# satstep6600.net
KiCad netlist of a schematic drawn in EAGLE
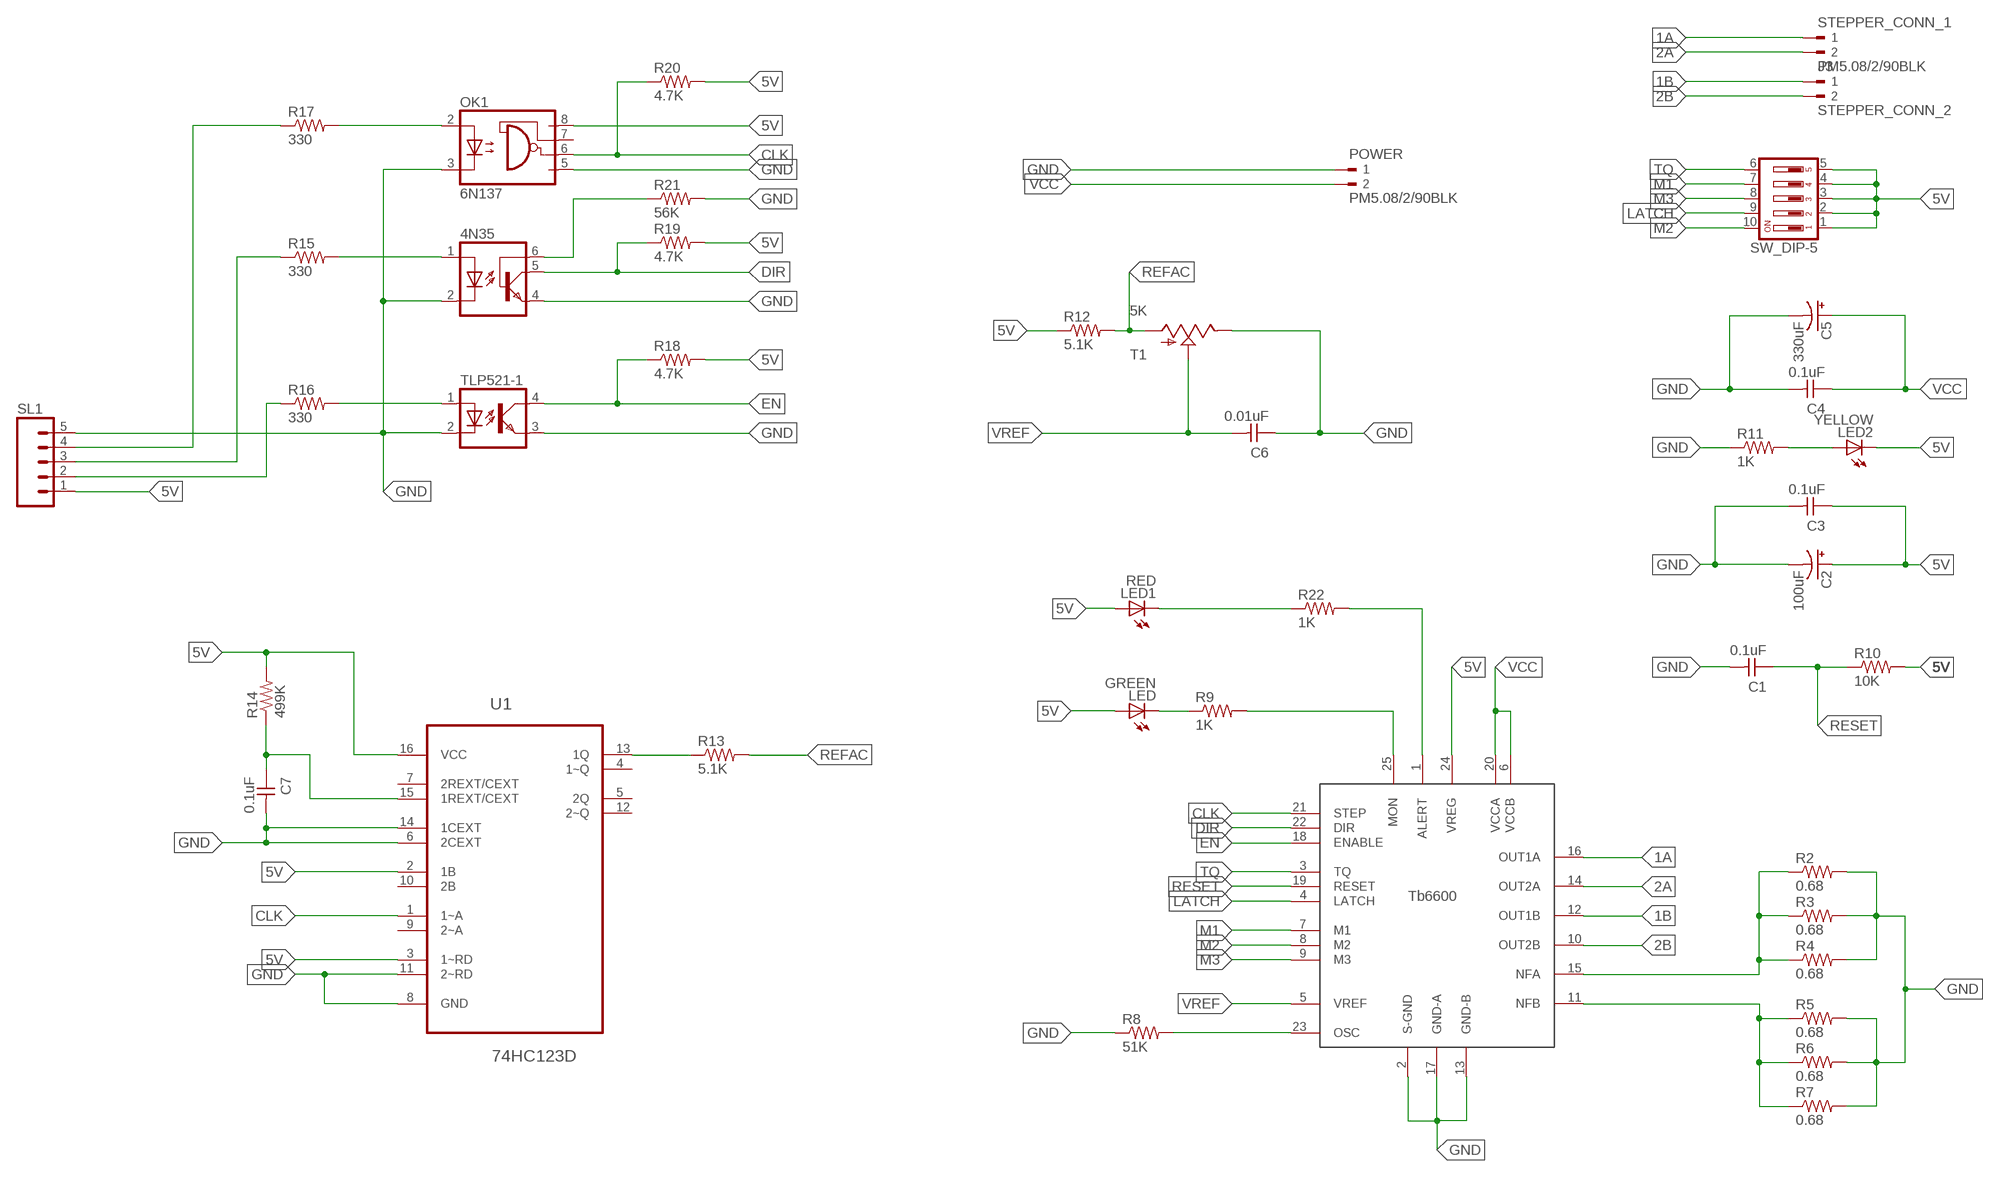
[diagram p0: schematic, sheet 1]

(export (version "E")
  (design (tool "Eeschema 10.0.6"))
  (components
    (comp (ref "4N35")
      (value "4N35")
      (footprint "eagle-import:DIL06")
      (libsource (lib "eagle-import") (part "4N35"))
    )
    (comp (ref "C1")
      (value "0.1uF")
      (footprint "eagle-import:1206")
      (libsource (lib "eagle-import") (part "UNPOLARIZED_CAPACITOR1206"))
    )
    (comp (ref "C2")
      (value "100uF")
      (footprint "eagle-import:PANASONIC_C")
      (libsource (lib "eagle-import") (part "CAP_POLC"))
    )
    (comp (ref "C3")
      (value "0.1uF")
      (footprint "eagle-import:1206")
      (libsource (lib "eagle-import") (part "UNPOLARIZED_CAPACITOR1206"))
    )
    (comp (ref "C4")
      (value "0.1uF")
      (footprint "eagle-import:1206")
      (libsource (lib "eagle-import") (part "UNPOLARIZED_CAPACITOR1206"))
    )
    (comp (ref "C5")
      (value "330uF")
      (footprint "eagle-import:CPOL-RADIAL-1000UF-63V")
      (libsource (lib "eagle-import") (part "CAP_POLPTH3"))
    )
    (comp (ref "C6")
      (value "0.01uF")
      (footprint "eagle-import:1206")
      (libsource (lib "eagle-import") (part "UNPOLARIZED_CAPACITOR1206"))
    )
    (comp (ref "C7")
      (value "0.1uF")
      (footprint "eagle-import:1206")
      (libsource (lib "eagle-import") (part "UNPOLARIZED_CAPACITOR1206"))
    )
    (comp (ref "J3")
      (value "STEPPER_CONN_2")
      (footprint "eagle-import:WEIDMULLER_PM5.08_2")
      (fields (field (name "MPN") "PM5.08/2/90 BLK"))
      (libsource (lib "eagle-import") (part "PM5.08/2/90BLK"))
    )
    (comp (ref "LED")
      (value "GREEN")
      (footprint "eagle-import:1206")
      (libsource (lib "eagle-import") (part "LED1206"))
    )
    (comp (ref "LED1")
      (value "RED")
      (footprint "eagle-import:1206")
      (libsource (lib "eagle-import") (part "LED1206"))
    )
    (comp (ref "LED2")
      (value "YELLOW")
      (footprint "eagle-import:1206")
      (libsource (lib "eagle-import") (part "LED1206"))
    )
    (comp (ref "OK1")
      (value "6N137")
      (footprint "eagle-import:DIL08")
      (libsource (lib "eagle-import") (part "6N137"))
    )
    (comp (ref "POWER")
      (value "PM5.08/2/90BLK")
      (footprint "eagle-import:WEIDMULLER_PM5.08_2")
      (fields (field (name "MPN") "PM5.08/2/90 BLK"))
      (libsource (lib "eagle-import") (part "PM5.08/2/90BLK"))
    )
    (comp (ref "R2")
      (value "0.68")
      (footprint "eagle-import:2512")
      (libsource (lib "eagle-import") (part "0.001OHM-3W-1%(2512)3W/1%"))
    )
    (comp (ref "R3")
      (value "0.68")
      (footprint "eagle-import:2512")
      (libsource (lib "eagle-import") (part "0.001OHM-3W-1%(2512)3W/1%"))
    )
    (comp (ref "R4")
      (value "0.68")
      (footprint "eagle-import:2512")
      (libsource (lib "eagle-import") (part "0.001OHM-3W-1%(2512)3W/1%"))
    )
    (comp (ref "R5")
      (value "0.68")
      (footprint "eagle-import:2512")
      (libsource (lib "eagle-import") (part "0.001OHM-3W-1%(2512)3W/1%"))
    )
    (comp (ref "R6")
      (value "0.68")
      (footprint "eagle-import:2512")
      (libsource (lib "eagle-import") (part "0.001OHM-3W-1%(2512)3W/1%"))
    )
    (comp (ref "R7")
      (value "0.68")
      (footprint "eagle-import:2512")
      (libsource (lib "eagle-import") (part "0.001OHM-3W-1%(2512)3W/1%"))
    )
    (comp (ref "R8")
      (value "51K")
      (footprint "eagle-import:R1206")
      (libsource (lib "eagle-import") (part "RES-US1206"))
    )
    (comp (ref "R9")
      (value "1K")
      (footprint "eagle-import:R1206")
      (libsource (lib "eagle-import") (part "RES-US1206"))
    )
    (comp (ref "R10")
      (value "10K")
      (footprint "eagle-import:R1206")
      (libsource (lib "eagle-import") (part "RES-US1206"))
    )
    (comp (ref "R11")
      (value "1K")
      (footprint "eagle-import:R1206")
      (libsource (lib "eagle-import") (part "RES-US1206"))
    )
    (comp (ref "R12")
      (value "5.1K")
      (footprint "eagle-import:R1206")
      (libsource (lib "eagle-import") (part "RES-US1206"))
    )
    (comp (ref "R13")
      (value "5.1K")
      (footprint "eagle-import:R1206")
      (libsource (lib "eagle-import") (part "RES-US1206"))
    )
    (comp (ref "R14")
      (value "499K")
      (footprint "eagle-import:R1206")
      (libsource (lib "eagle-import") (part "RES-US1206"))
    )
    (comp (ref "R15")
      (value "330")
      (footprint "eagle-import:R1206")
      (libsource (lib "eagle-import") (part "RES-US1206"))
    )
    (comp (ref "R16")
      (value "330")
      (footprint "eagle-import:R1206")
      (libsource (lib "eagle-import") (part "RES-US1206"))
    )
    (comp (ref "R17")
      (value "330")
      (footprint "eagle-import:R1206")
      (libsource (lib "eagle-import") (part "RES-US1206"))
    )
    (comp (ref "R18")
      (value "4.7K")
      (footprint "eagle-import:R1206")
      (libsource (lib "eagle-import") (part "RES-US1206"))
    )
    (comp (ref "R19")
      (value "4.7K")
      (footprint "eagle-import:R1206")
      (libsource (lib "eagle-import") (part "RES-US1206"))
    )
    (comp (ref "R20")
      (value "4.7K")
      (footprint "eagle-import:R1206")
      (libsource (lib "eagle-import") (part "RES-US1206"))
    )
    (comp (ref "R21")
      (value "56K")
      (footprint "eagle-import:R1206")
      (libsource (lib "eagle-import") (part "RES-US1206"))
    )
    (comp (ref "R22")
      (value "1K")
      (footprint "eagle-import:R1206")
      (libsource (lib "eagle-import") (part "RES-US1206"))
    )
    (comp (ref "SL1")
      (value "M05")
      (footprint "eagle-import:05P")
      (libsource (lib "eagle-import") (part "M05"))
    )
    (comp (ref "STEPPER_CONN_1")
      (value "PM5.08/2/90BLK")
      (footprint "eagle-import:WEIDMULLER_PM5.08_2")
      (fields (field (name "MPN") "PM5.08/2/90 BLK"))
      (libsource (lib "eagle-import") (part "PM5.08/2/90BLK"))
    )
    (comp (ref "SW_DIP-5")
      (value "SD4-05")
      (footprint "eagle-import:SD4-05")
      (libsource (lib "eagle-import") (part "SD4-05"))
    )
    (comp (ref "T1")
      (value "5K")
      (footprint "eagle-import:TS53YL104MR10_TRIMMER")
      (libsource (lib "eagle-import") (part "TS53YL104MR10-TRIMMER"))
    )
    (comp (ref "TLP521-1")
      (value "PC817")
      (footprint "eagle-import:DIL04")
      (libsource (lib "eagle-import") (part "PC817"))
    )
    (comp (ref "U$1")
      (value "TB6600HG")
      (footprint "eagle-import:P-HZIP25-1.00G")
      (libsource (lib "eagle-import") (part "TB6600HG"))
    )
    (comp (ref "U1")
      (value "74HC123D")
      (footprint "eagle-import:SOIC127P600X175-16N")
      (libsource (lib "eagle-import") (part "74HC123D"))
    )
  )
  (nets
    (net (code "1") (name "1A") (class "Default")
      (node (ref "STEPPER_CONN_1") (pin "1") (pinfunction "1_1") (pintype "passive"))
      (node (ref "U$1") (pin "16") (pinfunction "OUT1A_16") (pintype "output"))
    )
    (net (code "2") (name "1B") (class "Default")
      (node (ref "J3") (pin "1") (pinfunction "1_1") (pintype "passive"))
      (node (ref "U$1") (pin "12") (pinfunction "OUT1B_12") (pintype "output"))
    )
    (net (code "3") (name "2A") (class "Default")
      (node (ref "STEPPER_CONN_1") (pin "2") (pinfunction "2_2") (pintype "passive"))
      (node (ref "U$1") (pin "14") (pinfunction "OUT2A_14") (pintype "output"))
    )
    (net (code "4") (name "2B") (class "Default")
      (node (ref "J3") (pin "2") (pinfunction "2_2") (pintype "passive"))
      (node (ref "U$1") (pin "10") (pinfunction "OUT2B_10") (pintype "output"))
    )
    (net (code "5") (name "5V") (class "Default")
      (node (ref "C2") (pin "+") (pinfunction "+_+") (pintype "passive"))
      (node (ref "C3") (pin "1") (pinfunction "1_1") (pintype "passive"))
      (node (ref "LED") (pin "1") (pinfunction "A_1") (pintype "passive"))
      (node (ref "LED1") (pin "1") (pinfunction "A_1") (pintype "passive"))
      (node (ref "LED2") (pin "2") (pinfunction "C_2") (pintype "passive"))
      (node (ref "OK1") (pin "8") (pinfunction "VCC_8") (pintype "passive"))
      (node (ref "R10") (pin "2") (pinfunction "2_2") (pintype "passive"))
      (node (ref "R12") (pin "1") (pinfunction "1_1") (pintype "passive"))
      (node (ref "R14") (pin "2") (pinfunction "2_2") (pintype "passive"))
      (node (ref "R18") (pin "2") (pinfunction "2_2") (pintype "passive"))
      (node (ref "R19") (pin "2") (pinfunction "2_2") (pintype "passive"))
      (node (ref "R20") (pin "2") (pinfunction "2_2") (pintype "passive"))
      (node (ref "SL1") (pin "1") (pinfunction "1_1") (pintype "passive"))
      (node (ref "SW_DIP-5") (pin "1") (pinfunction "1_1") (pintype "passive"))
      (node (ref "SW_DIP-5") (pin "2") (pinfunction "2_2") (pintype "passive"))
      (node (ref "SW_DIP-5") (pin "3") (pinfunction "3_3") (pintype "passive"))
      (node (ref "SW_DIP-5") (pin "4") (pinfunction "4_4") (pintype "passive"))
      (node (ref "SW_DIP-5") (pin "5") (pinfunction "5_5") (pintype "passive"))
      (node (ref "U$1") (pin "24") (pinfunction "VREG_24") (pintype "output"))
      (node (ref "U1") (pin "16") (pinfunction "VCC_16") (pintype "power_in"))
      (node (ref "U1") (pin "2") (pinfunction "1B_2") (pintype "input"))
      (node (ref "U1") (pin "3") (pinfunction "1~{RD}_3") (pintype "input"))
    )
    (net (code "6") (name "CLK") (class "Default")
      (node (ref "OK1") (pin "6") (pinfunction "VO_6") (pintype "passive"))
      (node (ref "R20") (pin "1") (pinfunction "1_1") (pintype "passive"))
      (node (ref "U$1") (pin "21") (pinfunction "STEP_21") (pintype "input"))
      (node (ref "U1") (pin "1") (pinfunction "1~{A}_1") (pintype "input"))
    )
    (net (code "7") (name "DIR") (class "Default")
      (node (ref "4N35") (pin "5") (pinfunction "COL_5") (pintype "passive"))
      (node (ref "R19") (pin "1") (pinfunction "1_1") (pintype "passive"))
      (node (ref "U$1") (pin "22") (pinfunction "DIR_22") (pintype "input"))
    )
    (net (code "8") (name "EN") (class "Default")
      (node (ref "R18") (pin "1") (pinfunction "1_1") (pintype "passive"))
      (node (ref "TLP521-1") (pin "4") (pinfunction "COL_4") (pintype "passive"))
      (node (ref "U$1") (pin "18") (pinfunction "ENABLE_18") (pintype "input"))
    )
    (net (code "9") (name "GND") (class "Default")
      (node (ref "4N35") (pin "2") (pinfunction "C_2") (pintype "passive"))
      (node (ref "4N35") (pin "4") (pinfunction "EMI_4") (pintype "passive"))
      (node (ref "C1") (pin "2") (pinfunction "2_2") (pintype "passive"))
      (node (ref "C2") (pin "-") (pinfunction "-_-") (pintype "passive"))
      (node (ref "C3") (pin "2") (pinfunction "2_2") (pintype "passive"))
      (node (ref "C4") (pin "2") (pinfunction "2_2") (pintype "passive"))
      (node (ref "C5") (pin "2") (pinfunction "-_2") (pintype "passive"))
      (node (ref "C6") (pin "1") (pinfunction "1_1") (pintype "passive"))
      (node (ref "C7") (pin "2") (pinfunction "2_2") (pintype "passive"))
      (node (ref "OK1") (pin "3") (pinfunction "C_3") (pintype "passive"))
      (node (ref "OK1") (pin "5") (pinfunction "GND_5") (pintype "passive"))
      (node (ref "POWER") (pin "1") (pinfunction "1_1") (pintype "passive"))
      (node (ref "R11") (pin "1") (pinfunction "1_1") (pintype "passive"))
      (node (ref "R2") (pin "2") (pinfunction "2_2") (pintype "passive"))
      (node (ref "R21") (pin "2") (pinfunction "2_2") (pintype "passive"))
      (node (ref "R3") (pin "2") (pinfunction "2_2") (pintype "passive"))
      (node (ref "R4") (pin "2") (pinfunction "2_2") (pintype "passive"))
      (node (ref "R5") (pin "2") (pinfunction "2_2") (pintype "passive"))
      (node (ref "R6") (pin "2") (pinfunction "2_2") (pintype "passive"))
      (node (ref "R7") (pin "2") (pinfunction "2_2") (pintype "passive"))
      (node (ref "R8") (pin "1") (pinfunction "1_1") (pintype "passive"))
      (node (ref "SL1") (pin "5") (pinfunction "5_5") (pintype "passive"))
      (node (ref "T1") (pin "P$2") (pinfunction "E_P$2") (pintype "passive"))
      (node (ref "TLP521-1") (pin "2") (pinfunction "C_2") (pintype "passive"))
      (node (ref "TLP521-1") (pin "3") (pinfunction "EMIT_3") (pintype "passive"))
      (node (ref "U$1") (pin "13") (pinfunction "GND-B_13") (pintype "power_in"))
      (node (ref "U$1") (pin "17") (pinfunction "GND-A_17") (pintype "output"))
      (node (ref "U$1") (pin "2") (pinfunction "S-GND_2") (pintype "power_in"))
      (node (ref "U1") (pin "11") (pinfunction "2~{RD}_11") (pintype "input"))
      (node (ref "U1") (pin "14") (pinfunction "1CEXT_14") (pintype "passive"))
      (node (ref "U1") (pin "6") (pinfunction "2CEXT_6") (pintype "passive"))
      (node (ref "U1") (pin "8") (pinfunction "GND_8") (pintype "passive"))
    )
    (net (code "10") (name "LATCH") (class "Default")
      (node (ref "SW_DIP-5") (pin "9") (pinfunction "9_9") (pintype "passive"))
      (node (ref "U$1") (pin "4") (pinfunction "LATCH_4") (pintype "input"))
    )
    (net (code "11") (name "M1") (class "Default")
      (node (ref "SW_DIP-5") (pin "7") (pinfunction "7_7") (pintype "passive"))
      (node (ref "U$1") (pin "7") (pinfunction "M1_7") (pintype "input"))
    )
    (net (code "12") (name "M2") (class "Default")
      (node (ref "SW_DIP-5") (pin "10") (pinfunction "10_10") (pintype "passive"))
      (node (ref "U$1") (pin "8") (pinfunction "M2_8") (pintype "input"))
    )
    (net (code "13") (name "M3") (class "Default")
      (node (ref "SW_DIP-5") (pin "8") (pinfunction "8_8") (pintype "passive"))
      (node (ref "U$1") (pin "9") (pinfunction "M3_9") (pintype "input"))
    )
    (net (code "14") (name "Net-(4N35-A)") (class "Default")
      (node (ref "4N35") (pin "1") (pinfunction "A_1") (pintype "passive"))
      (node (ref "R15") (pin "2") (pinfunction "2_2") (pintype "passive"))
    )
    (net (code "15") (name "Net-(4N35-BAS)") (class "Default")
      (node (ref "4N35") (pin "6") (pinfunction "BAS_6") (pintype "passive"))
      (node (ref "R21") (pin "1") (pinfunction "1_1") (pintype "passive"))
    )
    (net (code "16") (name "Net-(LED-C)") (class "Default")
      (node (ref "LED") (pin "2") (pinfunction "C_2") (pintype "passive"))
      (node (ref "R9") (pin "1") (pinfunction "1_1") (pintype "passive"))
    )
    (net (code "17") (name "Net-(LED1-C)") (class "Default")
      (node (ref "LED1") (pin "2") (pinfunction "C_2") (pintype "passive"))
      (node (ref "R22") (pin "1") (pinfunction "1_1") (pintype "passive"))
    )
    (net (code "18") (name "Net-(LED2-A)") (class "Default")
      (node (ref "LED2") (pin "1") (pinfunction "A_1") (pintype "passive"))
      (node (ref "R11") (pin "2") (pinfunction "2_2") (pintype "passive"))
    )
    (net (code "19") (name "Net-(OK1-A)") (class "Default")
      (node (ref "OK1") (pin "2") (pinfunction "A_2") (pintype "passive"))
      (node (ref "R17") (pin "2") (pinfunction "2_2") (pintype "passive"))
    )
    (net (code "20") (name "Net-(R15-Pad1)") (class "Default")
      (node (ref "R15") (pin "1") (pinfunction "1_1") (pintype "passive"))
      (node (ref "SL1") (pin "3") (pinfunction "3_3") (pintype "passive"))
    )
    (net (code "21") (name "Net-(R16-Pad1)") (class "Default")
      (node (ref "R16") (pin "1") (pinfunction "1_1") (pintype "passive"))
      (node (ref "SL1") (pin "2") (pinfunction "2_2") (pintype "passive"))
    )
    (net (code "22") (name "Net-(R17-Pad1)") (class "Default")
      (node (ref "R17") (pin "1") (pinfunction "1_1") (pintype "passive"))
      (node (ref "SL1") (pin "4") (pinfunction "4_4") (pintype "passive"))
    )
    (net (code "23") (name "Net-(TLP521-1-A)") (class "Default")
      (node (ref "R16") (pin "2") (pinfunction "2_2") (pintype "passive"))
      (node (ref "TLP521-1") (pin "1") (pinfunction "A_1") (pintype "passive"))
    )
    (net (code "24") (name "Net-(U$1-ALERT)") (class "Default")
      (node (ref "R22") (pin "2") (pinfunction "2_2") (pintype "passive"))
      (node (ref "U$1") (pin "1") (pinfunction "ALERT_1") (pintype "output"))
    )
    (net (code "25") (name "Net-(U$1-MON)") (class "Default")
      (node (ref "R9") (pin "2") (pinfunction "2_2") (pintype "passive"))
      (node (ref "U$1") (pin "25") (pinfunction "MON_25") (pintype "output"))
    )
    (net (code "26") (name "Net-(U$1-NFA)") (class "Default")
      (node (ref "R2") (pin "1") (pinfunction "1_1") (pintype "passive"))
      (node (ref "R3") (pin "1") (pinfunction "1_1") (pintype "passive"))
      (node (ref "R4") (pin "1") (pinfunction "1_1") (pintype "passive"))
      (node (ref "U$1") (pin "15") (pinfunction "NFA_15") (pintype "input"))
    )
    (net (code "27") (name "Net-(U$1-NFB)") (class "Default")
      (node (ref "R5") (pin "1") (pinfunction "1_1") (pintype "passive"))
      (node (ref "R6") (pin "1") (pinfunction "1_1") (pintype "passive"))
      (node (ref "R7") (pin "1") (pinfunction "1_1") (pintype "passive"))
      (node (ref "U$1") (pin "11") (pinfunction "NFB_11") (pintype "input"))
    )
    (net (code "28") (name "Net-(U$1-OSC)") (class "Default")
      (node (ref "R8") (pin "2") (pinfunction "2_2") (pintype "passive"))
      (node (ref "U$1") (pin "23") (pinfunction "OSC_23") (pintype "input"))
    )
    (net (code "29") (name "Net-(U1-1Q)") (class "Default")
      (node (ref "R13") (pin "1") (pinfunction "1_1") (pintype "passive"))
      (node (ref "U1") (pin "13") (pinfunction "1Q_13") (pintype "output"))
    )
    (net (code "30") (name "Net-(U1-1REXT{slash}CEXT)") (class "Default")
      (node (ref "C7") (pin "1") (pinfunction "1_1") (pintype "passive"))
      (node (ref "R14") (pin "1") (pinfunction "1_1") (pintype "passive"))
      (node (ref "U1") (pin "15") (pinfunction "1REXT/CEXT_15") (pintype "passive"))
    )
    (net (code "31") (name "REFAC") (class "Default")
      (node (ref "R12") (pin "2") (pinfunction "2_2") (pintype "passive"))
      (node (ref "R13") (pin "2") (pinfunction "2_2") (pintype "passive"))
      (node (ref "T1") (pin "P$3") (pinfunction "A_P$3") (pintype "passive"))
    )
    (net (code "32") (name "RESET") (class "Default")
      (node (ref "C1") (pin "1") (pinfunction "1_1") (pintype "passive"))
      (node (ref "R10") (pin "1") (pinfunction "1_1") (pintype "passive"))
      (node (ref "U$1") (pin "19") (pinfunction "RESET_19") (pintype "input"))
    )
    (net (code "33") (name "TQ") (class "Default")
      (node (ref "SW_DIP-5") (pin "6") (pinfunction "6_6") (pintype "passive"))
      (node (ref "U$1") (pin "3") (pinfunction "TQ_3") (pintype "input"))
    )
    (net (code "34") (name "VCC") (class "Default")
      (node (ref "C4") (pin "1") (pinfunction "1_1") (pintype "passive"))
      (node (ref "C5") (pin "1") (pinfunction "+_1") (pintype "passive"))
      (node (ref "POWER") (pin "2") (pinfunction "2_2") (pintype "passive"))
      (node (ref "U$1") (pin "20") (pinfunction "VCCA_20") (pintype "power_in"))
      (node (ref "U$1") (pin "6") (pinfunction "VCCB_6") (pintype "power_in"))
    )
    (net (code "35") (name "VREF") (class "Default")
      (node (ref "C6") (pin "2") (pinfunction "2_2") (pintype "passive"))
      (node (ref "T1") (pin "P$1") (pinfunction "S_P$1") (pintype "passive"))
      (node (ref "U$1") (pin "5") (pinfunction "VREF_5") (pintype "input"))
    )
    (net (code "36") (name "unconnected-(OK1-VE-Pad7)") (class "Default")
      (node (ref "OK1") (pin "7") (pinfunction "VE_7") (pintype "passive"))
    )
    (net (code "37") (name "unconnected-(U1-1~{Q}-Pad4)") (class "Default")
      (node (ref "U1") (pin "4") (pinfunction "1~{Q}_4") (pintype "output"))
    )
    (net (code "38") (name "unconnected-(U1-2B-Pad10)") (class "Default")
      (node (ref "U1") (pin "10") (pinfunction "2B_10") (pintype "input"))
    )
    (net (code "39") (name "unconnected-(U1-2Q-Pad5)") (class "Default")
      (node (ref "U1") (pin "5") (pinfunction "2Q_5") (pintype "output"))
    )
    (net (code "40") (name "unconnected-(U1-2REXT{slash}CEXT-Pad7)") (class "Default")
      (node (ref "U1") (pin "7") (pinfunction "2REXT/CEXT_7") (pintype "passive"))
    )
    (net (code "41") (name "unconnected-(U1-2~{A}-Pad9)") (class "Default")
      (node (ref "U1") (pin "9") (pinfunction "2~{A}_9") (pintype "input"))
    )
    (net (code "42") (name "unconnected-(U1-2~{Q}-Pad12)") (class "Default")
      (node (ref "U1") (pin "12") (pinfunction "2~{Q}_12") (pintype "output"))
    )
  )
)
